# VIDEOCONV_TC358870.net
KiCad netlist of a schematic drawn in Altium Designer
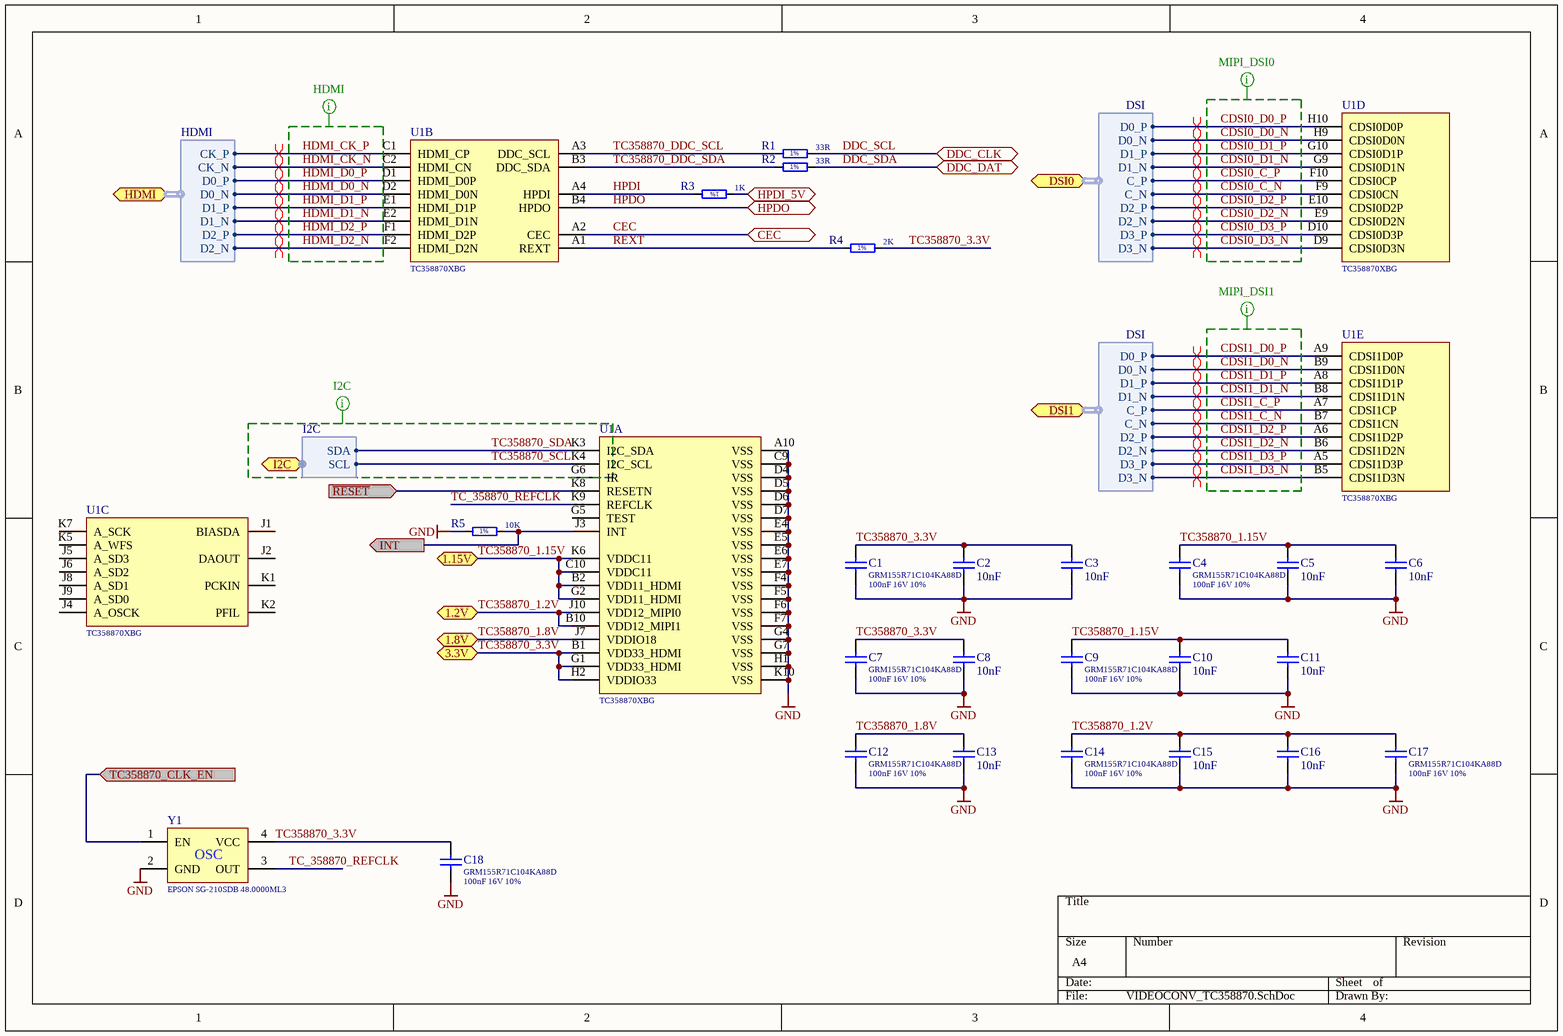
[diagram p0: VIDEOCONV_TC358870.SchDoc]

(export (version "E")
  (design (tool "Eeschema 10.0.6"))
  (components
    (comp (ref "C1")
      (value "GRM155R71C104KA88D")
      (footprint "CAP_SMD:0402")
      (description "Ceramic capacitor")
      (fields
        (field (name "VOLTAGE") "16V")
        (field (name "TOLERANCE") "10%")
        (field (name "ALTIUM_VALUE") "100nF 16V 10%")
      )
      (libsource (lib "Passive") (part "Capacitor ceramic"))
    )
    (comp (ref "C2")
      (value "10nF")
      (footprint "CHIP_SMD:0402C")
      (description "Ceramic capacitor")
      (fields (field (name "TOLERANCE") "10%") (field (name "VOLTAGE") "50V"))
      (libsource (lib "Passive") (part "Capacitor ceramic"))
    )
    (comp (ref "C3")
      (value "10nF")
      (footprint "CHIP_SMD:0402C")
      (description "Ceramic capacitor")
      (fields (field (name "TOLERANCE") "10%") (field (name "VOLTAGE") "50V"))
      (libsource (lib "Passive") (part "Capacitor ceramic"))
    )
    (comp (ref "C4")
      (value "GRM155R71C104KA88D")
      (footprint "CAP_SMD:0402")
      (description "Ceramic capacitor")
      (fields
        (field (name "VOLTAGE") "16V")
        (field (name "TOLERANCE") "10%")
        (field (name "ALTIUM_VALUE") "100nF 16V 10%")
      )
      (libsource (lib "Passive") (part "Capacitor ceramic"))
    )
    (comp (ref "C5")
      (value "10nF")
      (footprint "CHIP_SMD:0402C")
      (description "Ceramic capacitor")
      (fields (field (name "TOLERANCE") "10%") (field (name "VOLTAGE") "50V"))
      (libsource (lib "Passive") (part "Capacitor ceramic"))
    )
    (comp (ref "C6")
      (value "10nF")
      (footprint "CHIP_SMD:0402C")
      (description "Ceramic capacitor")
      (fields (field (name "TOLERANCE") "10%") (field (name "VOLTAGE") "50V"))
      (libsource (lib "Passive") (part "Capacitor ceramic"))
    )
    (comp (ref "C7")
      (value "GRM155R71C104KA88D")
      (footprint "CAP_SMD:0402")
      (description "Ceramic capacitor")
      (fields
        (field (name "VOLTAGE") "16V")
        (field (name "TOLERANCE") "10%")
        (field (name "ALTIUM_VALUE") "100nF 16V 10%")
      )
      (libsource (lib "Passive") (part "Capacitor ceramic"))
    )
    (comp (ref "C8")
      (value "10nF")
      (footprint "CHIP_SMD:0402C")
      (description "Ceramic capacitor")
      (fields (field (name "TOLERANCE") "10%") (field (name "VOLTAGE") "50V"))
      (libsource (lib "Passive") (part "Capacitor ceramic"))
    )
    (comp (ref "C9")
      (value "GRM155R71C104KA88D")
      (footprint "CAP_SMD:0402")
      (description "Ceramic capacitor")
      (fields
        (field (name "VOLTAGE") "16V")
        (field (name "TOLERANCE") "10%")
        (field (name "ALTIUM_VALUE") "100nF 16V 10%")
      )
      (libsource (lib "Passive") (part "Capacitor ceramic"))
    )
    (comp (ref "C10")
      (value "10nF")
      (footprint "CHIP_SMD:0402C")
      (description "Ceramic capacitor")
      (fields (field (name "TOLERANCE") "10%") (field (name "VOLTAGE") "50V"))
      (libsource (lib "Passive") (part "Capacitor ceramic"))
    )
    (comp (ref "C11")
      (value "10nF")
      (footprint "CHIP_SMD:0402C")
      (description "Ceramic capacitor")
      (fields (field (name "TOLERANCE") "10%") (field (name "VOLTAGE") "50V"))
      (libsource (lib "Passive") (part "Capacitor ceramic"))
    )
    (comp (ref "C12")
      (value "GRM155R71C104KA88D")
      (footprint "CAP_SMD:0402")
      (description "Ceramic capacitor")
      (fields
        (field (name "VOLTAGE") "16V")
        (field (name "TOLERANCE") "10%")
        (field (name "ALTIUM_VALUE") "100nF 16V 10%")
      )
      (libsource (lib "Passive") (part "Capacitor ceramic"))
    )
    (comp (ref "C13")
      (value "10nF")
      (footprint "CHIP_SMD:0402C")
      (description "Ceramic capacitor")
      (fields (field (name "TOLERANCE") "10%") (field (name "VOLTAGE") "50V"))
      (libsource (lib "Passive") (part "Capacitor ceramic"))
    )
    (comp (ref "C14")
      (value "GRM155R71C104KA88D")
      (footprint "CAP_SMD:0402")
      (description "Ceramic capacitor")
      (fields
        (field (name "VOLTAGE") "16V")
        (field (name "TOLERANCE") "10%")
        (field (name "ALTIUM_VALUE") "100nF 16V 10%")
      )
      (libsource (lib "Passive") (part "Capacitor ceramic"))
    )
    (comp (ref "C15")
      (value "10nF")
      (footprint "CHIP_SMD:0402C")
      (description "Ceramic capacitor")
      (fields (field (name "TOLERANCE") "10%") (field (name "VOLTAGE") "50V"))
      (libsource (lib "Passive") (part "Capacitor ceramic"))
    )
    (comp (ref "C16")
      (value "10nF")
      (footprint "CHIP_SMD:0402C")
      (description "Ceramic capacitor")
      (fields (field (name "TOLERANCE") "10%") (field (name "VOLTAGE") "50V"))
      (libsource (lib "Passive") (part "Capacitor ceramic"))
    )
    (comp (ref "C17")
      (value "GRM155R71C104KA88D")
      (footprint "CAP_SMD:0402")
      (description "Ceramic capacitor")
      (fields
        (field (name "VOLTAGE") "16V")
        (field (name "TOLERANCE") "10%")
        (field (name "ALTIUM_VALUE") "100nF 16V 10%")
      )
      (libsource (lib "Passive") (part "Capacitor ceramic"))
    )
    (comp (ref "C18")
      (value "GRM155R71C104KA88D")
      (footprint "CAP_SMD:0402")
      (description "Ceramic capacitor")
      (fields
        (field (name "VOLTAGE") "16V")
        (field (name "TOLERANCE") "10%")
        (field (name "ALTIUM_VALUE") "100nF 16V 10%")
      )
      (libsource (lib "Passive") (part "Capacitor ceramic"))
    )
    (comp (ref "R1")
      (value "33R")
      (footprint "CHIP_SMD:0402R")
      (description "Thin Film Chip Resistor")
      (fields (field (name "POWER") "0.1 W") (field (name "TOLERANCE") "1%"))
      (libsource (lib "Passive") (part "Resistor 1%"))
    )
    (comp (ref "R2")
      (value "33R")
      (footprint "CHIP_SMD:0402R")
      (description "Thin Film Chip Resistor")
      (fields (field (name "POWER") "0.1 W") (field (name "TOLERANCE") "1%"))
      (libsource (lib "Passive") (part "Resistor 1%"))
    )
    (comp (ref "R3")
      (value "1K")
      (footprint "CHIP_SMD:0402R")
      (description "Thin Film Chip Resistor")
      (fields (field (name "POWER") "0.1 W") (field (name "TOLERANCE") "1%"))
      (libsource (lib "Passive") (part "Resistor 1%"))
    )
    (comp (ref "R4")
      (value "2K")
      (footprint "CHIP_SMD:0402R")
      (description "Thin Film Chip Resistor")
      (fields (field (name "POWER") "0.1 W") (field (name "TOLERANCE") "1%"))
      (libsource (lib "Passive") (part "Resistor 1%"))
    )
    (comp (ref "R5")
      (value "10K")
      (footprint "CHIP_SMD:0402R")
      (description "Thin Film Chip Resistor")
      (fields (field (name "POWER") "0.1 W") (field (name "TOLERANCE") "1%"))
      (libsource (lib "Passive") (part "Resistor 1%"))
    )
    (comp (ref "U1")
      (value "TC358870XBG")
      (footprint "CSP_BGA:VFBGA-80-0707-0.65")
      (description "Ultra HD to dual DSI bridge")
      (libsource (lib "IC_HDMI") (part "TC358870XBG"))
    )
    (comp (ref "Y1")
      (value "EPSON SG-210SDB 48.0000ML3")
      (footprint "CRYSTAL_OSC:2025")
      (description "Oscillator")
      (libsource (lib "Crystal_Osc") (part "Oscillator"))
    )
  )
  (nets
    (net (code "4") (name "/CDSI0_C_N") (class "Default")
      (node (ref "U1") (pin "F9") (pinfunction "CDSI0CN_F9") (pintype "passive"))
    )
    (net (code "5") (name "/CDSI0_C_P") (class "Default")
      (node (ref "U1") (pin "F10") (pinfunction "CDSI0CP_F10") (pintype "passive"))
    )
    (net (code "6") (name "/CDSI0_D0_N") (class "Default")
      (node (ref "U1") (pin "H9") (pinfunction "CDSI0D0N_H9") (pintype "passive"))
    )
    (net (code "7") (name "/CDSI0_D0_P") (class "Default")
      (node (ref "U1") (pin "H10") (pinfunction "CDSI0D0P_H10") (pintype "passive"))
    )
    (net (code "8") (name "/CDSI0_D1_N") (class "Default")
      (node (ref "U1") (pin "G9") (pinfunction "CDSI0D1N_G9") (pintype "passive"))
    )
    (net (code "9") (name "/CDSI0_D1_P") (class "Default")
      (node (ref "U1") (pin "G10") (pinfunction "CDSI0D1P_G10") (pintype "passive"))
    )
    (net (code "10") (name "/CDSI0_D2_N") (class "Default")
      (node (ref "U1") (pin "E9") (pinfunction "CDSI0D2N_E9") (pintype "passive"))
    )
    (net (code "11") (name "/CDSI0_D2_P") (class "Default")
      (node (ref "U1") (pin "E10") (pinfunction "CDSI0D2P_E10") (pintype "passive"))
    )
    (net (code "12") (name "/CDSI0_D3_N") (class "Default")
      (node (ref "U1") (pin "D9") (pinfunction "CDSI0D3N_D9") (pintype "passive"))
    )
    (net (code "13") (name "/CDSI0_D3_P") (class "Default")
      (node (ref "U1") (pin "D10") (pinfunction "CDSI0D3P_D10") (pintype "passive"))
    )
    (net (code "14") (name "/CDSI1_C_N") (class "Default")
      (node (ref "U1") (pin "B7") (pinfunction "CDSI1CN_B7") (pintype "passive"))
    )
    (net (code "15") (name "/CDSI1_C_P") (class "Default")
      (node (ref "U1") (pin "A7") (pinfunction "CDSI1CP_A7") (pintype "passive"))
    )
    (net (code "16") (name "/CDSI1_D0_N") (class "Default")
      (node (ref "U1") (pin "B9") (pinfunction "CDSI1D0N_B9") (pintype "passive"))
    )
    (net (code "17") (name "/CDSI1_D0_P") (class "Default")
      (node (ref "U1") (pin "A9") (pinfunction "CDSI1D0P_A9") (pintype "passive"))
    )
    (net (code "18") (name "/CDSI1_D1_N") (class "Default")
      (node (ref "U1") (pin "B8") (pinfunction "CDSI1D1N_B8") (pintype "passive"))
    )
    (net (code "19") (name "/CDSI1_D1_P") (class "Default")
      (node (ref "U1") (pin "A8") (pinfunction "CDSI1D1P_A8") (pintype "passive"))
    )
    (net (code "20") (name "/CDSI1_D2_N") (class "Default")
      (node (ref "U1") (pin "B6") (pinfunction "CDSI1D2N_B6") (pintype "passive"))
    )
    (net (code "21") (name "/CDSI1_D2_P") (class "Default")
      (node (ref "U1") (pin "A6") (pinfunction "CDSI1D2P_A6") (pintype "passive"))
    )
    (net (code "22") (name "/CDSI1_D3_N") (class "Default")
      (node (ref "U1") (pin "B5") (pinfunction "CDSI1D3N_B5") (pintype "passive"))
    )
    (net (code "23") (name "/CDSI1_D3_P") (class "Default")
      (node (ref "U1") (pin "A5") (pinfunction "CDSI1D3P_A5") (pintype "passive"))
    )
    (net (code "24") (name "/CEC") (class "Default")
      (node (ref "U1") (pin "A2") (pinfunction "CEC_A2") (pintype "passive"))
    )
    (net (code "25") (name "/DDC_SCL") (class "Default")
      (node (ref "R1") (pin "2") (pinfunction "2_2") (pintype "passive"))
    )
    (net (code "26") (name "/DDC_SDA") (class "Default")
      (node (ref "R2") (pin "2") (pinfunction "2_2") (pintype "passive"))
    )
    (net (code "27") (name "/HDMI_CK_N") (class "Default")
      (node (ref "U1") (pin "C2") (pinfunction "HDMI_CN_C2") (pintype "passive"))
    )
    (net (code "28") (name "/HDMI_CK_P") (class "Default")
      (node (ref "U1") (pin "C1") (pinfunction "HDMI_CP_C1") (pintype "passive"))
    )
    (net (code "29") (name "/HDMI_D0_N") (class "Default")
      (node (ref "U1") (pin "D2") (pinfunction "HDMI_D0N_D2") (pintype "passive"))
    )
    (net (code "30") (name "/HDMI_D0_P") (class "Default")
      (node (ref "U1") (pin "D1") (pinfunction "HDMI_D0P_D1") (pintype "passive"))
    )
    (net (code "31") (name "/HDMI_D1_N") (class "Default")
      (node (ref "U1") (pin "E2") (pinfunction "HDMI_D1N_E2") (pintype "passive"))
    )
    (net (code "32") (name "/HDMI_D1_P") (class "Default")
      (node (ref "U1") (pin "E1") (pinfunction "HDMI_D1P_E1") (pintype "passive"))
    )
    (net (code "33") (name "/HDMI_D2_N") (class "Default")
      (node (ref "U1") (pin "F2") (pinfunction "HDMI_D2N_F2") (pintype "passive"))
    )
    (net (code "34") (name "/HDMI_D2_P") (class "Default")
      (node (ref "U1") (pin "F1") (pinfunction "HDMI_D2P_F1") (pintype "passive"))
    )
    (net (code "35") (name "/HPDI") (class "Default")
      (node (ref "R3") (pin "2") (pinfunction "2_2") (pintype "passive"))
      (node (ref "U1") (pin "A4") (pinfunction "HPDI_A4") (pintype "passive"))
    )
    (net (code "36") (name "/HPDI_5V") (class "Default")
      (node (ref "R3") (pin "1") (pinfunction "1_1") (pintype "passive"))
    )
    (net (code "37") (name "/HPDO") (class "Default")
      (node (ref "U1") (pin "B4") (pinfunction "HPDO_B4") (pintype "passive"))
    )
    (net (code "38") (name "/INT") (class "Default")
      (node (ref "R5") (pin "2") (pinfunction "2_2") (pintype "passive"))
      (node (ref "U1") (pin "J3") (pinfunction "INT_J3") (pintype "passive"))
    )
    (net (code "39") (name "/REXT") (class "Default")
      (node (ref "R4") (pin "1") (pinfunction "1_1") (pintype "passive"))
      (node (ref "U1") (pin "A1") (pinfunction "REXT_A1") (pintype "passive"))
    )
    (net (code "40") (name "/TC358870_1.2V") (class "Default")
      (node (ref "C14") (pin "1") (pinfunction "1_1") (pintype "passive"))
      (node (ref "C15") (pin "2") (pinfunction "2_2") (pintype "passive"))
      (node (ref "C16") (pin "2") (pinfunction "2_2") (pintype "passive"))
      (node (ref "C17") (pin "1") (pinfunction "1_1") (pintype "passive"))
      (node (ref "U1") (pin "B10") (pinfunction "VDD12_MIPI1_B10") (pintype "passive"))
      (node (ref "U1") (pin "J10") (pinfunction "VDD12_MIPI0_J10") (pintype "passive"))
    )
    (net (code "41") (name "/TC358870_1.8V") (class "Default")
      (node (ref "C12") (pin "1") (pinfunction "1_1") (pintype "passive"))
      (node (ref "C13") (pin "2") (pinfunction "2_2") (pintype "passive"))
      (node (ref "U1") (pin "J7") (pinfunction "VDDIO18_J7") (pintype "passive"))
    )
    (net (code "42") (name "/TC358870_1.15V") (class "Default")
      (node (ref "C10") (pin "2") (pinfunction "2_2") (pintype "passive"))
      (node (ref "C11") (pin "2") (pinfunction "2_2") (pintype "passive"))
      (node (ref "C4") (pin "1") (pinfunction "1_1") (pintype "passive"))
      (node (ref "C5") (pin "2") (pinfunction "2_2") (pintype "passive"))
      (node (ref "C6") (pin "2") (pinfunction "2_2") (pintype "passive"))
      (node (ref "C9") (pin "1") (pinfunction "1_1") (pintype "passive"))
      (node (ref "U1") (pin "B2") (pinfunction "VDD11_HDMI_B2") (pintype "passive"))
      (node (ref "U1") (pin "C10") (pinfunction "VDDC11_C10") (pintype "passive"))
      (node (ref "U1") (pin "G2") (pinfunction "VDD11_HDMI_G2") (pintype "passive"))
      (node (ref "U1") (pin "K6") (pinfunction "VDDC11_K6") (pintype "passive"))
    )
    (net (code "43") (name "/TC358870_3.3V") (class "Default")
      (node (ref "C1") (pin "1") (pinfunction "1_1") (pintype "passive"))
      (node (ref "C18") (pin "1") (pinfunction "1_1") (pintype "passive"))
      (node (ref "C2") (pin "2") (pinfunction "2_2") (pintype "passive"))
      (node (ref "C3") (pin "2") (pinfunction "2_2") (pintype "passive"))
      (node (ref "C7") (pin "1") (pinfunction "1_1") (pintype "passive"))
      (node (ref "C8") (pin "2") (pinfunction "2_2") (pintype "passive"))
      (node (ref "R4") (pin "2") (pinfunction "2_2") (pintype "passive"))
      (node (ref "U1") (pin "B1") (pinfunction "VDD33_HDMI_B1") (pintype "passive"))
      (node (ref "U1") (pin "G1") (pinfunction "VDD33_HDMI_G1") (pintype "passive"))
      (node (ref "U1") (pin "H2") (pinfunction "VDDIO33_H2") (pintype "passive"))
      (node (ref "Y1") (pin "4") (pinfunction "VCC_4") (pintype "power_in"))
    )
    (net (code "44") (name "/TC358870_CLK_EN") (class "Default")
      (node (ref "Y1") (pin "1") (pinfunction "EN_1") (pintype "passive"))
    )
    (net (code "45") (name "/TC358870_DDC_SCL") (class "Default")
      (node (ref "R1") (pin "1") (pinfunction "1_1") (pintype "passive"))
      (node (ref "U1") (pin "A3") (pinfunction "DDC_SCL_A3") (pintype "passive"))
    )
    (net (code "46") (name "/TC358870_DDC_SDA") (class "Default")
      (node (ref "R2") (pin "1") (pinfunction "1_1") (pintype "passive"))
      (node (ref "U1") (pin "B3") (pinfunction "DDC_SDA_B3") (pintype "passive"))
    )
    (net (code "47") (name "/TC358870_SCL") (class "Default")
      (node (ref "U1") (pin "K4") (pinfunction "I2C_SCL_K4") (pintype "passive"))
    )
    (net (code "48") (name "/TC358870_SDA") (class "Default")
      (node (ref "U1") (pin "K3") (pinfunction "I2C_SDA_K3") (pintype "passive"))
    )
    (net (code "49") (name "/TC_358870_REFCLK") (class "Default")
      (node (ref "U1") (pin "K9") (pinfunction "REFCLK_K9") (pintype "passive"))
      (node (ref "Y1") (pin "3") (pinfunction "OUT_3") (pintype "passive"))
    )
    (net (code "53") (name "/~{RESET}") (class "Default")
      (node (ref "U1") (pin "K8") (pinfunction "RESETN_K8") (pintype "passive"))
    )
    (net (code "54") (name "GND") (class "Default")
      (node (ref "C1") (pin "2") (pinfunction "2_2") (pintype "passive"))
      (node (ref "C10") (pin "1") (pinfunction "1_1") (pintype "passive"))
      (node (ref "C11") (pin "1") (pinfunction "1_1") (pintype "passive"))
      (node (ref "C12") (pin "2") (pinfunction "2_2") (pintype "passive"))
      (node (ref "C13") (pin "1") (pinfunction "1_1") (pintype "passive"))
      (node (ref "C14") (pin "2") (pinfunction "2_2") (pintype "passive"))
      (node (ref "C15") (pin "1") (pinfunction "1_1") (pintype "passive"))
      (node (ref "C16") (pin "1") (pinfunction "1_1") (pintype "passive"))
      (node (ref "C17") (pin "2") (pinfunction "2_2") (pintype "passive"))
      (node (ref "C18") (pin "2") (pinfunction "2_2") (pintype "passive"))
      (node (ref "C2") (pin "1") (pinfunction "1_1") (pintype "passive"))
      (node (ref "C3") (pin "1") (pinfunction "1_1") (pintype "passive"))
      (node (ref "C4") (pin "2") (pinfunction "2_2") (pintype "passive"))
      (node (ref "C5") (pin "1") (pinfunction "1_1") (pintype "passive"))
      (node (ref "C6") (pin "1") (pinfunction "1_1") (pintype "passive"))
      (node (ref "C7") (pin "2") (pinfunction "2_2") (pintype "passive"))
      (node (ref "C8") (pin "1") (pinfunction "1_1") (pintype "passive"))
      (node (ref "C9") (pin "2") (pinfunction "2_2") (pintype "passive"))
      (node (ref "R5") (pin "1") (pinfunction "1_1") (pintype "passive"))
      (node (ref "U1") (pin "A10") (pinfunction "VSS_A10") (pintype "passive"))
      (node (ref "U1") (pin "C9") (pinfunction "VSS_C9") (pintype "passive"))
      (node (ref "U1") (pin "D4") (pinfunction "VSS_D4") (pintype "passive"))
      (node (ref "U1") (pin "D5") (pinfunction "VSS_D5") (pintype "passive"))
      (node (ref "U1") (pin "D6") (pinfunction "VSS_D6") (pintype "passive"))
      (node (ref "U1") (pin "D7") (pinfunction "VSS_D7") (pintype "passive"))
      (node (ref "U1") (pin "E4") (pinfunction "VSS_E4") (pintype "passive"))
      (node (ref "U1") (pin "E5") (pinfunction "VSS_E5") (pintype "passive"))
      (node (ref "U1") (pin "E6") (pinfunction "VSS_E6") (pintype "passive"))
      (node (ref "U1") (pin "E7") (pinfunction "VSS_E7") (pintype "passive"))
      (node (ref "U1") (pin "F4") (pinfunction "VSS_F4") (pintype "passive"))
      (node (ref "U1") (pin "F5") (pinfunction "VSS_F5") (pintype "passive"))
      (node (ref "U1") (pin "F6") (pinfunction "VSS_F6") (pintype "passive"))
      (node (ref "U1") (pin "F7") (pinfunction "VSS_F7") (pintype "passive"))
      (node (ref "U1") (pin "G4") (pinfunction "VSS_G4") (pintype "passive"))
      (node (ref "U1") (pin "G7") (pinfunction "VSS_G7") (pintype "passive"))
      (node (ref "U1") (pin "H1") (pinfunction "VSS_H1") (pintype "passive"))
      (node (ref "U1") (pin "K10") (pinfunction "VSS_K10") (pintype "passive"))
      (node (ref "Y1") (pin "2") (pinfunction "GND_2") (pintype "power_in"))
    )
    (net (code "55") (name "unconnected-(U1A-IR-PadG6)") (class "Default")
      (node (ref "U1") (pin "G6") (pinfunction "IR_G6") (pintype "passive"))
    )
    (net (code "56") (name "unconnected-(U1A-TEST-PadG5)") (class "Default")
      (node (ref "U1") (pin "G5") (pinfunction "TEST_G5") (pintype "passive"))
    )
    (net (code "57") (name "unconnected-(U1C-A_OSCK-PadJ4)") (class "Default")
      (node (ref "U1") (pin "J4") (pinfunction "A_OSCK_J4") (pintype "passive"))
    )
    (net (code "58") (name "unconnected-(U1C-A_SCK-PadK7)") (class "Default")
      (node (ref "U1") (pin "K7") (pinfunction "A_SCK_K7") (pintype "passive"))
    )
    (net (code "59") (name "unconnected-(U1C-A_SD0-PadJ9)") (class "Default")
      (node (ref "U1") (pin "J9") (pinfunction "A_SD0_J9") (pintype "passive"))
    )
    (net (code "60") (name "unconnected-(U1C-A_SD1-PadJ8)") (class "Default")
      (node (ref "U1") (pin "J8") (pinfunction "A_SD1_J8") (pintype "passive"))
    )
    (net (code "61") (name "unconnected-(U1C-A_SD2-PadJ6)") (class "Default")
      (node (ref "U1") (pin "J6") (pinfunction "A_SD2_J6") (pintype "passive"))
    )
    (net (code "62") (name "unconnected-(U1C-A_SD3-PadJ5)") (class "Default")
      (node (ref "U1") (pin "J5") (pinfunction "A_SD3_J5") (pintype "passive"))
    )
    (net (code "63") (name "unconnected-(U1C-A_WFS-PadK5)") (class "Default")
      (node (ref "U1") (pin "K5") (pinfunction "A_WFS_K5") (pintype "passive"))
    )
    (net (code "64") (name "unconnected-(U1C-BIASDA-PadJ1)") (class "Default")
      (node (ref "U1") (pin "J1") (pinfunction "BIASDA_J1") (pintype "passive"))
    )
    (net (code "65") (name "unconnected-(U1C-DAOUT-PadJ2)") (class "Default")
      (node (ref "U1") (pin "J2") (pinfunction "DAOUT_J2") (pintype "passive"))
    )
    (net (code "66") (name "unconnected-(U1C-PCKIN-PadK1)") (class "Default")
      (node (ref "U1") (pin "K1") (pinfunction "PCKIN_K1") (pintype "passive"))
    )
    (net (code "67") (name "unconnected-(U1C-PFIL-PadK2)") (class "Default")
      (node (ref "U1") (pin "K2") (pinfunction "PFIL_K2") (pintype "passive"))
    )
  )
)
